# PSSI2021SAY_breakout.net
KiCad netlist of a schematic drawn in Altium Designer
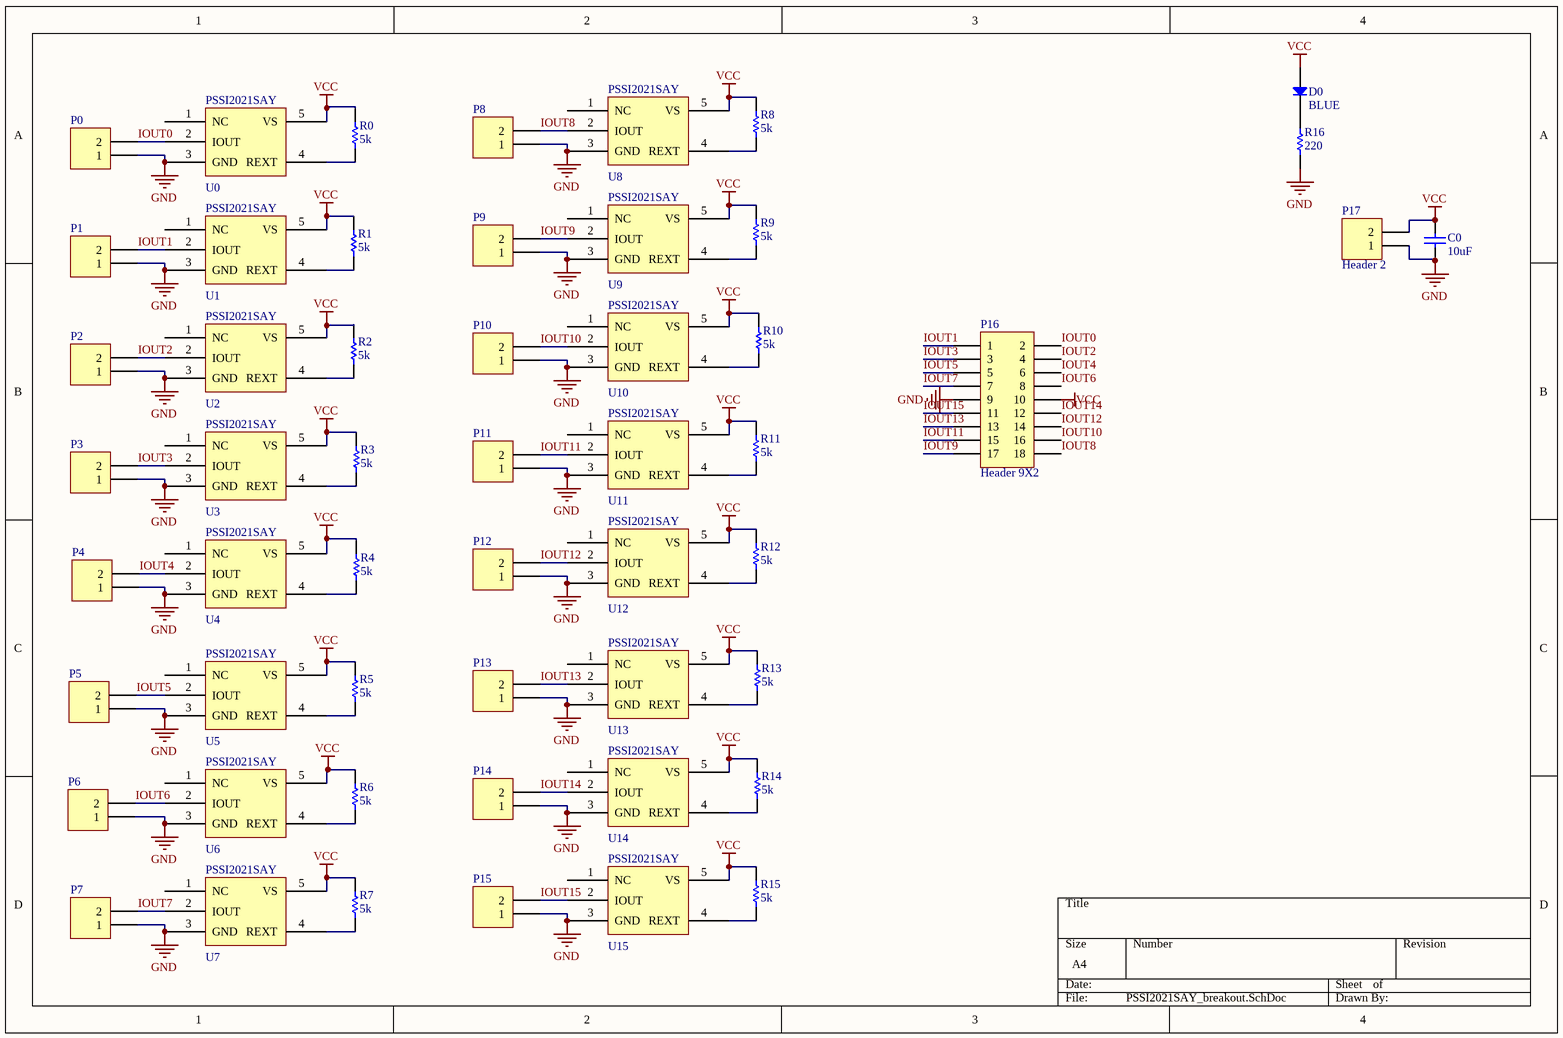
[diagram p0: PSSI2021SAY_breakout.SchDoc]

(export (version "E")
  (design (tool "Eeschema 10.0.6"))
  (components
    (comp (ref "C0")
      (value "10uF")
      (footprint "0805_CAP")
      (description "Chip Capacitor")
      (libsource (lib "ailabLib") (part "CAP_SMD"))
    )
    (comp (ref "D0") (value "BLUE") (footprint "0603_LED") (libsource (lib "ailabLib") (part "LED_SMD")))
    (comp (ref "P0")
      (value "S0")
      (footprint "HDR1X2")
      (description "Header, 2-Pin")
      (fields (field (name "PUBLISHER") "Altium Limited"))
      (libsource (lib "Miscellaneous Connectors") (part "Header 2"))
    )
    (comp (ref "P1")
      (value "S0")
      (footprint "HDR1X2")
      (description "Header, 2-Pin")
      (fields (field (name "PUBLISHER") "Altium Limited"))
      (libsource (lib "Miscellaneous Connectors") (part "Header 2"))
    )
    (comp (ref "P2")
      (value "S0")
      (footprint "HDR1X2")
      (description "Header, 2-Pin")
      (fields (field (name "PUBLISHER") "Altium Limited"))
      (libsource (lib "Miscellaneous Connectors") (part "Header 2"))
    )
    (comp (ref "P3")
      (value "S0")
      (footprint "HDR1X2")
      (description "Header, 2-Pin")
      (fields (field (name "PUBLISHER") "Altium Limited"))
      (libsource (lib "Miscellaneous Connectors") (part "Header 2"))
    )
    (comp (ref "P4")
      (value "S0")
      (footprint "HDR1X2")
      (description "Header, 2-Pin")
      (fields (field (name "PUBLISHER") "Altium Limited"))
      (libsource (lib "Miscellaneous Connectors") (part "Header 2"))
    )
    (comp (ref "P5")
      (value "S0")
      (footprint "HDR1X2")
      (description "Header, 2-Pin")
      (fields (field (name "PUBLISHER") "Altium Limited"))
      (libsource (lib "Miscellaneous Connectors") (part "Header 2"))
    )
    (comp (ref "P6")
      (value "S0")
      (footprint "HDR1X2")
      (description "Header, 2-Pin")
      (fields (field (name "PUBLISHER") "Altium Limited"))
      (libsource (lib "Miscellaneous Connectors") (part "Header 2"))
    )
    (comp (ref "P7")
      (value "S0")
      (footprint "HDR1X2")
      (description "Header, 2-Pin")
      (fields (field (name "PUBLISHER") "Altium Limited"))
      (libsource (lib "Miscellaneous Connectors") (part "Header 2"))
    )
    (comp (ref "P8")
      (value "S0")
      (footprint "HDR1X2")
      (description "Header, 2-Pin")
      (fields (field (name "PUBLISHER") "Altium Limited"))
      (libsource (lib "Miscellaneous Connectors") (part "Header 2"))
    )
    (comp (ref "P9")
      (value "S0")
      (footprint "HDR1X2")
      (description "Header, 2-Pin")
      (fields (field (name "PUBLISHER") "Altium Limited"))
      (libsource (lib "Miscellaneous Connectors") (part "Header 2"))
    )
    (comp (ref "P10")
      (value "S0")
      (footprint "HDR1X2")
      (description "Header, 2-Pin")
      (fields (field (name "PUBLISHER") "Altium Limited"))
      (libsource (lib "Miscellaneous Connectors") (part "Header 2"))
    )
    (comp (ref "P11")
      (value "S0")
      (footprint "HDR1X2")
      (description "Header, 2-Pin")
      (fields (field (name "PUBLISHER") "Altium Limited"))
      (libsource (lib "Miscellaneous Connectors") (part "Header 2"))
    )
    (comp (ref "P12")
      (value "S0")
      (footprint "HDR1X2")
      (description "Header, 2-Pin")
      (fields (field (name "PUBLISHER") "Altium Limited"))
      (libsource (lib "Miscellaneous Connectors") (part "Header 2"))
    )
    (comp (ref "P13")
      (value "S0")
      (footprint "HDR1X2")
      (description "Header, 2-Pin")
      (fields (field (name "PUBLISHER") "Altium Limited"))
      (libsource (lib "Miscellaneous Connectors") (part "Header 2"))
    )
    (comp (ref "P14")
      (value "S0")
      (footprint "HDR1X2")
      (description "Header, 2-Pin")
      (fields (field (name "PUBLISHER") "Altium Limited"))
      (libsource (lib "Miscellaneous Connectors") (part "Header 2"))
    )
    (comp (ref "P15")
      (value "S0")
      (footprint "HDR1X2")
      (description "Header, 2-Pin")
      (fields (field (name "PUBLISHER") "Altium Limited"))
      (libsource (lib "Miscellaneous Connectors") (part "Header 2"))
    )
    (comp (ref "P16")
      (value "Header 9X2")
      (footprint "HDR2X9")
      (description "Header, 9-Pin, Dual row")
      (fields (field (name "PUBLISHER") "Altium Limited"))
      (libsource (lib "Miscellaneous Connectors") (part "Header 9X2"))
    )
    (comp (ref "P17")
      (value "Header 2")
      (footprint "HDR1X2")
      (description "Header, 2-Pin")
      (fields (field (name "PUBLISHER") "Altium Limited"))
      (libsource (lib "Miscellaneous Connectors") (part "Header 2"))
    )
    (comp (ref "R0") (value "5k") (footprint "0603_RES") (libsource (lib "ailabLib") (part "RES_SMD")))
    (comp (ref "R1") (value "5k") (footprint "0603_RES") (libsource (lib "ailabLib") (part "RES_SMD")))
    (comp (ref "R2") (value "5k") (footprint "0603_RES") (libsource (lib "ailabLib") (part "RES_SMD")))
    (comp (ref "R3") (value "5k") (footprint "0603_RES") (libsource (lib "ailabLib") (part "RES_SMD")))
    (comp (ref "R4") (value "5k") (footprint "0603_RES") (libsource (lib "ailabLib") (part "RES_SMD")))
    (comp (ref "R5") (value "5k") (footprint "0603_RES") (libsource (lib "ailabLib") (part "RES_SMD")))
    (comp (ref "R6") (value "5k") (footprint "0603_RES") (libsource (lib "ailabLib") (part "RES_SMD")))
    (comp (ref "R7") (value "5k") (footprint "0603_RES") (libsource (lib "ailabLib") (part "RES_SMD")))
    (comp (ref "R8") (value "5k") (footprint "0603_RES") (libsource (lib "ailabLib") (part "RES_SMD")))
    (comp (ref "R9") (value "5k") (footprint "0603_RES") (libsource (lib "ailabLib") (part "RES_SMD")))
    (comp (ref "R10") (value "5k") (footprint "0603_RES") (libsource (lib "ailabLib") (part "RES_SMD")))
    (comp (ref "R11") (value "5k") (footprint "0603_RES") (libsource (lib "ailabLib") (part "RES_SMD")))
    (comp (ref "R12") (value "5k") (footprint "0603_RES") (libsource (lib "ailabLib") (part "RES_SMD")))
    (comp (ref "R13") (value "5k") (footprint "0603_RES") (libsource (lib "ailabLib") (part "RES_SMD")))
    (comp (ref "R14") (value "5k") (footprint "0603_RES") (libsource (lib "ailabLib") (part "RES_SMD")))
    (comp (ref "R15") (value "5k") (footprint "0603_RES") (libsource (lib "ailabLib") (part "RES_SMD")))
    (comp (ref "R16") (value "220") (footprint "0603_RES") (libsource (lib "ailabLib") (part "RES_SMD")))
    (comp (ref "U0")
      (value "PSSI2021SAY")
      (footprint "SOT65P210X110-5N")
      (libsource (lib "ailabLib") (part "PSSI2021SAY"))
    )
    (comp (ref "U1")
      (value "PSSI2021SAY")
      (footprint "SOT65P210X110-5N")
      (libsource (lib "ailabLib") (part "PSSI2021SAY"))
    )
    (comp (ref "U2")
      (value "PSSI2021SAY")
      (footprint "SOT65P210X110-5N")
      (libsource (lib "ailabLib") (part "PSSI2021SAY"))
    )
    (comp (ref "U3")
      (value "PSSI2021SAY")
      (footprint "SOT65P210X110-5N")
      (libsource (lib "ailabLib") (part "PSSI2021SAY"))
    )
    (comp (ref "U4")
      (value "PSSI2021SAY")
      (footprint "SOT65P210X110-5N")
      (libsource (lib "ailabLib") (part "PSSI2021SAY"))
    )
    (comp (ref "U5")
      (value "PSSI2021SAY")
      (footprint "SOT65P210X110-5N")
      (libsource (lib "ailabLib") (part "PSSI2021SAY"))
    )
    (comp (ref "U6")
      (value "PSSI2021SAY")
      (footprint "SOT65P210X110-5N")
      (libsource (lib "ailabLib") (part "PSSI2021SAY"))
    )
    (comp (ref "U7")
      (value "PSSI2021SAY")
      (footprint "SOT65P210X110-5N")
      (libsource (lib "ailabLib") (part "PSSI2021SAY"))
    )
    (comp (ref "U8")
      (value "PSSI2021SAY")
      (footprint "SOT65P210X110-5N")
      (libsource (lib "ailabLib") (part "PSSI2021SAY"))
    )
    (comp (ref "U9")
      (value "PSSI2021SAY")
      (footprint "SOT65P210X110-5N")
      (libsource (lib "ailabLib") (part "PSSI2021SAY"))
    )
    (comp (ref "U10")
      (value "PSSI2021SAY")
      (footprint "SOT65P210X110-5N")
      (libsource (lib "ailabLib") (part "PSSI2021SAY"))
    )
    (comp (ref "U11")
      (value "PSSI2021SAY")
      (footprint "SOT65P210X110-5N")
      (libsource (lib "ailabLib") (part "PSSI2021SAY"))
    )
    (comp (ref "U12")
      (value "PSSI2021SAY")
      (footprint "SOT65P210X110-5N")
      (libsource (lib "ailabLib") (part "PSSI2021SAY"))
    )
    (comp (ref "U13")
      (value "PSSI2021SAY")
      (footprint "SOT65P210X110-5N")
      (libsource (lib "ailabLib") (part "PSSI2021SAY"))
    )
    (comp (ref "U14")
      (value "PSSI2021SAY")
      (footprint "SOT65P210X110-5N")
      (libsource (lib "ailabLib") (part "PSSI2021SAY"))
    )
    (comp (ref "U15")
      (value "PSSI2021SAY")
      (footprint "SOT65P210X110-5N")
      (libsource (lib "ailabLib") (part "PSSI2021SAY"))
    )
  )
  (nets
    (net (code "1") (name "/IOUT0") (class "Default")
      (node (ref "P0") (pin "2") (pinfunction "2_2") (pintype "passive"))
      (node (ref "P16") (pin "2") (pinfunction "2_2") (pintype "passive"))
      (node (ref "U0") (pin "2") (pinfunction "IOUT_2") (pintype "passive"))
    )
    (net (code "2") (name "/IOUT1") (class "Default")
      (node (ref "P1") (pin "2") (pinfunction "2_2") (pintype "passive"))
      (node (ref "P16") (pin "1") (pinfunction "1_1") (pintype "passive"))
      (node (ref "U1") (pin "2") (pinfunction "IOUT_2") (pintype "passive"))
    )
    (net (code "3") (name "/IOUT2") (class "Default")
      (node (ref "P16") (pin "4") (pinfunction "4_4") (pintype "passive"))
      (node (ref "P2") (pin "2") (pinfunction "2_2") (pintype "passive"))
      (node (ref "U2") (pin "2") (pinfunction "IOUT_2") (pintype "passive"))
    )
    (net (code "4") (name "/IOUT3") (class "Default")
      (node (ref "P16") (pin "3") (pinfunction "3_3") (pintype "passive"))
      (node (ref "P3") (pin "2") (pinfunction "2_2") (pintype "passive"))
      (node (ref "U3") (pin "2") (pinfunction "IOUT_2") (pintype "passive"))
    )
    (net (code "5") (name "/IOUT4") (class "Default")
      (node (ref "P16") (pin "6") (pinfunction "6_6") (pintype "passive"))
      (node (ref "P4") (pin "2") (pinfunction "2_2") (pintype "passive"))
      (node (ref "U4") (pin "2") (pinfunction "IOUT_2") (pintype "passive"))
    )
    (net (code "6") (name "/IOUT5") (class "Default")
      (node (ref "P16") (pin "5") (pinfunction "5_5") (pintype "passive"))
      (node (ref "P5") (pin "2") (pinfunction "2_2") (pintype "passive"))
      (node (ref "U5") (pin "2") (pinfunction "IOUT_2") (pintype "passive"))
    )
    (net (code "7") (name "/IOUT6") (class "Default")
      (node (ref "P16") (pin "8") (pinfunction "8_8") (pintype "passive"))
      (node (ref "P6") (pin "2") (pinfunction "2_2") (pintype "passive"))
      (node (ref "U6") (pin "2") (pinfunction "IOUT_2") (pintype "passive"))
    )
    (net (code "8") (name "/IOUT7") (class "Default")
      (node (ref "P16") (pin "7") (pinfunction "7_7") (pintype "passive"))
      (node (ref "P7") (pin "2") (pinfunction "2_2") (pintype "passive"))
      (node (ref "U7") (pin "2") (pinfunction "IOUT_2") (pintype "passive"))
    )
    (net (code "9") (name "/IOUT8") (class "Default")
      (node (ref "P16") (pin "18") (pinfunction "18_18") (pintype "passive"))
      (node (ref "P8") (pin "2") (pinfunction "2_2") (pintype "passive"))
      (node (ref "U8") (pin "2") (pinfunction "IOUT_2") (pintype "passive"))
    )
    (net (code "10") (name "/IOUT9") (class "Default")
      (node (ref "P16") (pin "17") (pinfunction "17_17") (pintype "passive"))
      (node (ref "P9") (pin "2") (pinfunction "2_2") (pintype "passive"))
      (node (ref "U9") (pin "2") (pinfunction "IOUT_2") (pintype "passive"))
    )
    (net (code "11") (name "/IOUT10") (class "Default")
      (node (ref "P10") (pin "2") (pinfunction "2_2") (pintype "passive"))
      (node (ref "P16") (pin "16") (pinfunction "16_16") (pintype "passive"))
      (node (ref "U10") (pin "2") (pinfunction "IOUT_2") (pintype "passive"))
    )
    (net (code "12") (name "/IOUT11") (class "Default")
      (node (ref "P11") (pin "2") (pinfunction "2_2") (pintype "passive"))
      (node (ref "P16") (pin "15") (pinfunction "15_15") (pintype "passive"))
      (node (ref "U11") (pin "2") (pinfunction "IOUT_2") (pintype "passive"))
    )
    (net (code "13") (name "/IOUT12") (class "Default")
      (node (ref "P12") (pin "2") (pinfunction "2_2") (pintype "passive"))
      (node (ref "P16") (pin "14") (pinfunction "14_14") (pintype "passive"))
      (node (ref "U12") (pin "2") (pinfunction "IOUT_2") (pintype "passive"))
    )
    (net (code "14") (name "/IOUT13") (class "Default")
      (node (ref "P13") (pin "2") (pinfunction "2_2") (pintype "passive"))
      (node (ref "P16") (pin "13") (pinfunction "13_13") (pintype "passive"))
      (node (ref "U13") (pin "2") (pinfunction "IOUT_2") (pintype "passive"))
    )
    (net (code "15") (name "/IOUT14") (class "Default")
      (node (ref "P14") (pin "2") (pinfunction "2_2") (pintype "passive"))
      (node (ref "P16") (pin "12") (pinfunction "12_12") (pintype "passive"))
      (node (ref "U14") (pin "2") (pinfunction "IOUT_2") (pintype "passive"))
    )
    (net (code "16") (name "/IOUT15") (class "Default")
      (node (ref "P15") (pin "2") (pinfunction "2_2") (pintype "passive"))
      (node (ref "P16") (pin "11") (pinfunction "11_11") (pintype "passive"))
      (node (ref "U15") (pin "2") (pinfunction "IOUT_2") (pintype "passive"))
    )
    (net (code "17") (name "GND") (class "Default")
      (node (ref "C0") (pin "1") (pinfunction "1_1") (pintype "passive"))
      (node (ref "P0") (pin "1") (pinfunction "1_1") (pintype "passive"))
      (node (ref "P1") (pin "1") (pinfunction "1_1") (pintype "passive"))
      (node (ref "P10") (pin "1") (pinfunction "1_1") (pintype "passive"))
      (node (ref "P11") (pin "1") (pinfunction "1_1") (pintype "passive"))
      (node (ref "P12") (pin "1") (pinfunction "1_1") (pintype "passive"))
      (node (ref "P13") (pin "1") (pinfunction "1_1") (pintype "passive"))
      (node (ref "P14") (pin "1") (pinfunction "1_1") (pintype "passive"))
      (node (ref "P15") (pin "1") (pinfunction "1_1") (pintype "passive"))
      (node (ref "P16") (pin "9") (pinfunction "9_9") (pintype "passive"))
      (node (ref "P17") (pin "1") (pinfunction "1_1") (pintype "passive"))
      (node (ref "P2") (pin "1") (pinfunction "1_1") (pintype "passive"))
      (node (ref "P3") (pin "1") (pinfunction "1_1") (pintype "passive"))
      (node (ref "P4") (pin "1") (pinfunction "1_1") (pintype "passive"))
      (node (ref "P5") (pin "1") (pinfunction "1_1") (pintype "passive"))
      (node (ref "P6") (pin "1") (pinfunction "1_1") (pintype "passive"))
      (node (ref "P7") (pin "1") (pinfunction "1_1") (pintype "passive"))
      (node (ref "P8") (pin "1") (pinfunction "1_1") (pintype "passive"))
      (node (ref "P9") (pin "1") (pinfunction "1_1") (pintype "passive"))
      (node (ref "R16") (pin "1") (pinfunction "1_1") (pintype "passive"))
      (node (ref "U0") (pin "3") (pinfunction "GND_3") (pintype "passive"))
      (node (ref "U1") (pin "3") (pinfunction "GND_3") (pintype "passive"))
      (node (ref "U10") (pin "3") (pinfunction "GND_3") (pintype "passive"))
      (node (ref "U11") (pin "3") (pinfunction "GND_3") (pintype "passive"))
      (node (ref "U12") (pin "3") (pinfunction "GND_3") (pintype "passive"))
      (node (ref "U13") (pin "3") (pinfunction "GND_3") (pintype "passive"))
      (node (ref "U14") (pin "3") (pinfunction "GND_3") (pintype "passive"))
      (node (ref "U15") (pin "3") (pinfunction "GND_3") (pintype "passive"))
      (node (ref "U2") (pin "3") (pinfunction "GND_3") (pintype "passive"))
      (node (ref "U3") (pin "3") (pinfunction "GND_3") (pintype "passive"))
      (node (ref "U4") (pin "3") (pinfunction "GND_3") (pintype "passive"))
      (node (ref "U5") (pin "3") (pinfunction "GND_3") (pintype "passive"))
      (node (ref "U6") (pin "3") (pinfunction "GND_3") (pintype "passive"))
      (node (ref "U7") (pin "3") (pinfunction "GND_3") (pintype "passive"))
      (node (ref "U8") (pin "3") (pinfunction "GND_3") (pintype "passive"))
      (node (ref "U9") (pin "3") (pinfunction "GND_3") (pintype "passive"))
    )
    (net (code "18") (name "Net-(D0-K)") (class "Default")
      (node (ref "D0") (pin "2") (pinfunction "K_2") (pintype "passive"))
      (node (ref "R16") (pin "2") (pinfunction "2_2") (pintype "passive"))
    )
    (net (code "19") (name "Net-(U0-REXT)") (class "Default")
      (node (ref "R0") (pin "1") (pinfunction "1_1") (pintype "passive"))
      (node (ref "U0") (pin "4") (pinfunction "REXT_4") (pintype "passive"))
    )
    (net (code "20") (name "Net-(U1-REXT)") (class "Default")
      (node (ref "R1") (pin "1") (pinfunction "1_1") (pintype "passive"))
      (node (ref "U1") (pin "4") (pinfunction "REXT_4") (pintype "passive"))
    )
    (net (code "21") (name "Net-(U2-REXT)") (class "Default")
      (node (ref "R2") (pin "1") (pinfunction "1_1") (pintype "passive"))
      (node (ref "U2") (pin "4") (pinfunction "REXT_4") (pintype "passive"))
    )
    (net (code "22") (name "Net-(U3-REXT)") (class "Default")
      (node (ref "R3") (pin "1") (pinfunction "1_1") (pintype "passive"))
      (node (ref "U3") (pin "4") (pinfunction "REXT_4") (pintype "passive"))
    )
    (net (code "23") (name "Net-(U4-REXT)") (class "Default")
      (node (ref "R4") (pin "1") (pinfunction "1_1") (pintype "passive"))
      (node (ref "U4") (pin "4") (pinfunction "REXT_4") (pintype "passive"))
    )
    (net (code "24") (name "Net-(U5-REXT)") (class "Default")
      (node (ref "R5") (pin "1") (pinfunction "1_1") (pintype "passive"))
      (node (ref "U5") (pin "4") (pinfunction "REXT_4") (pintype "passive"))
    )
    (net (code "25") (name "Net-(U6-REXT)") (class "Default")
      (node (ref "R6") (pin "1") (pinfunction "1_1") (pintype "passive"))
      (node (ref "U6") (pin "4") (pinfunction "REXT_4") (pintype "passive"))
    )
    (net (code "26") (name "Net-(U7-REXT)") (class "Default")
      (node (ref "R7") (pin "1") (pinfunction "1_1") (pintype "passive"))
      (node (ref "U7") (pin "4") (pinfunction "REXT_4") (pintype "passive"))
    )
    (net (code "27") (name "Net-(U8-REXT)") (class "Default")
      (node (ref "R8") (pin "1") (pinfunction "1_1") (pintype "passive"))
      (node (ref "U8") (pin "4") (pinfunction "REXT_4") (pintype "passive"))
    )
    (net (code "28") (name "Net-(U9-REXT)") (class "Default")
      (node (ref "R9") (pin "1") (pinfunction "1_1") (pintype "passive"))
      (node (ref "U9") (pin "4") (pinfunction "REXT_4") (pintype "passive"))
    )
    (net (code "29") (name "Net-(U10-REXT)") (class "Default")
      (node (ref "R10") (pin "1") (pinfunction "1_1") (pintype "passive"))
      (node (ref "U10") (pin "4") (pinfunction "REXT_4") (pintype "passive"))
    )
    (net (code "30") (name "Net-(U11-REXT)") (class "Default")
      (node (ref "R11") (pin "1") (pinfunction "1_1") (pintype "passive"))
      (node (ref "U11") (pin "4") (pinfunction "REXT_4") (pintype "passive"))
    )
    (net (code "31") (name "Net-(U12-REXT)") (class "Default")
      (node (ref "R12") (pin "1") (pinfunction "1_1") (pintype "passive"))
      (node (ref "U12") (pin "4") (pinfunction "REXT_4") (pintype "passive"))
    )
    (net (code "32") (name "Net-(U13-REXT)") (class "Default")
      (node (ref "R13") (pin "1") (pinfunction "1_1") (pintype "passive"))
      (node (ref "U13") (pin "4") (pinfunction "REXT_4") (pintype "passive"))
    )
    (net (code "33") (name "Net-(U14-REXT)") (class "Default")
      (node (ref "R14") (pin "1") (pinfunction "1_1") (pintype "passive"))
      (node (ref "U14") (pin "4") (pinfunction "REXT_4") (pintype "passive"))
    )
    (net (code "34") (name "Net-(U15-REXT)") (class "Default")
      (node (ref "R15") (pin "1") (pinfunction "1_1") (pintype "passive"))
      (node (ref "U15") (pin "4") (pinfunction "REXT_4") (pintype "passive"))
    )
    (net (code "35") (name "VCC") (class "Default")
      (node (ref "C0") (pin "2") (pinfunction "2_2") (pintype "passive"))
      (node (ref "D0") (pin "1") (pinfunction "A_1") (pintype "passive"))
      (node (ref "P16") (pin "10") (pinfunction "10_10") (pintype "passive"))
      (node (ref "P17") (pin "2") (pinfunction "2_2") (pintype "passive"))
      (node (ref "R0") (pin "2") (pinfunction "2_2") (pintype "passive"))
      (node (ref "R1") (pin "2") (pinfunction "2_2") (pintype "passive"))
      (node (ref "R10") (pin "2") (pinfunction "2_2") (pintype "passive"))
      (node (ref "R11") (pin "2") (pinfunction "2_2") (pintype "passive"))
      (node (ref "R12") (pin "2") (pinfunction "2_2") (pintype "passive"))
      (node (ref "R13") (pin "2") (pinfunction "2_2") (pintype "passive"))
      (node (ref "R14") (pin "2") (pinfunction "2_2") (pintype "passive"))
      (node (ref "R15") (pin "2") (pinfunction "2_2") (pintype "passive"))
      (node (ref "R2") (pin "2") (pinfunction "2_2") (pintype "passive"))
      (node (ref "R3") (pin "2") (pinfunction "2_2") (pintype "passive"))
      (node (ref "R4") (pin "2") (pinfunction "2_2") (pintype "passive"))
      (node (ref "R5") (pin "2") (pinfunction "2_2") (pintype "passive"))
      (node (ref "R6") (pin "2") (pinfunction "2_2") (pintype "passive"))
      (node (ref "R7") (pin "2") (pinfunction "2_2") (pintype "passive"))
      (node (ref "R8") (pin "2") (pinfunction "2_2") (pintype "passive"))
      (node (ref "R9") (pin "2") (pinfunction "2_2") (pintype "passive"))
      (node (ref "U0") (pin "5") (pinfunction "VS_5") (pintype "passive"))
      (node (ref "U1") (pin "5") (pinfunction "VS_5") (pintype "passive"))
      (node (ref "U10") (pin "5") (pinfunction "VS_5") (pintype "passive"))
      (node (ref "U11") (pin "5") (pinfunction "VS_5") (pintype "passive"))
      (node (ref "U12") (pin "5") (pinfunction "VS_5") (pintype "passive"))
      (node (ref "U13") (pin "5") (pinfunction "VS_5") (pintype "passive"))
      (node (ref "U14") (pin "5") (pinfunction "VS_5") (pintype "passive"))
      (node (ref "U15") (pin "5") (pinfunction "VS_5") (pintype "passive"))
      (node (ref "U2") (pin "5") (pinfunction "VS_5") (pintype "passive"))
      (node (ref "U3") (pin "5") (pinfunction "VS_5") (pintype "passive"))
      (node (ref "U4") (pin "5") (pinfunction "VS_5") (pintype "passive"))
      (node (ref "U5") (pin "5") (pinfunction "VS_5") (pintype "passive"))
      (node (ref "U6") (pin "5") (pinfunction "VS_5") (pintype "passive"))
      (node (ref "U7") (pin "5") (pinfunction "VS_5") (pintype "passive"))
      (node (ref "U8") (pin "5") (pinfunction "VS_5") (pintype "passive"))
      (node (ref "U9") (pin "5") (pinfunction "VS_5") (pintype "passive"))
    )
    (net (code "36") (name "unconnected-(U0-NC-Pad1)") (class "Default")
      (node (ref "U0") (pin "1") (pinfunction "NC_1") (pintype "passive"))
    )
    (net (code "37") (name "unconnected-(U1-NC-Pad1)") (class "Default")
      (node (ref "U1") (pin "1") (pinfunction "NC_1") (pintype "passive"))
    )
    (net (code "38") (name "unconnected-(U2-NC-Pad1)") (class "Default")
      (node (ref "U2") (pin "1") (pinfunction "NC_1") (pintype "passive"))
    )
    (net (code "39") (name "unconnected-(U3-NC-Pad1)") (class "Default")
      (node (ref "U3") (pin "1") (pinfunction "NC_1") (pintype "passive"))
    )
    (net (code "40") (name "unconnected-(U4-NC-Pad1)") (class "Default")
      (node (ref "U4") (pin "1") (pinfunction "NC_1") (pintype "passive"))
    )
    (net (code "41") (name "unconnected-(U5-NC-Pad1)") (class "Default")
      (node (ref "U5") (pin "1") (pinfunction "NC_1") (pintype "passive"))
    )
    (net (code "42") (name "unconnected-(U6-NC-Pad1)") (class "Default")
      (node (ref "U6") (pin "1") (pinfunction "NC_1") (pintype "passive"))
    )
    (net (code "43") (name "unconnected-(U7-NC-Pad1)") (class "Default")
      (node (ref "U7") (pin "1") (pinfunction "NC_1") (pintype "passive"))
    )
    (net (code "44") (name "unconnected-(U8-NC-Pad1)") (class "Default")
      (node (ref "U8") (pin "1") (pinfunction "NC_1") (pintype "passive"))
    )
    (net (code "45") (name "unconnected-(U9-NC-Pad1)") (class "Default")
      (node (ref "U9") (pin "1") (pinfunction "NC_1") (pintype "passive"))
    )
    (net (code "46") (name "unconnected-(U10-NC-Pad1)") (class "Default")
      (node (ref "U10") (pin "1") (pinfunction "NC_1") (pintype "passive"))
    )
    (net (code "47") (name "unconnected-(U11-NC-Pad1)") (class "Default")
      (node (ref "U11") (pin "1") (pinfunction "NC_1") (pintype "passive"))
    )
    (net (code "48") (name "unconnected-(U12-NC-Pad1)") (class "Default")
      (node (ref "U12") (pin "1") (pinfunction "NC_1") (pintype "passive"))
    )
    (net (code "49") (name "unconnected-(U13-NC-Pad1)") (class "Default")
      (node (ref "U13") (pin "1") (pinfunction "NC_1") (pintype "passive"))
    )
    (net (code "50") (name "unconnected-(U14-NC-Pad1)") (class "Default")
      (node (ref "U14") (pin "1") (pinfunction "NC_1") (pintype "passive"))
    )
    (net (code "51") (name "unconnected-(U15-NC-Pad1)") (class "Default")
      (node (ref "U15") (pin "1") (pinfunction "NC_1") (pintype "passive"))
    )
  )
)
